# lis2dh_spi.net
KiCad netlist of a schematic drawn in Altium Designer
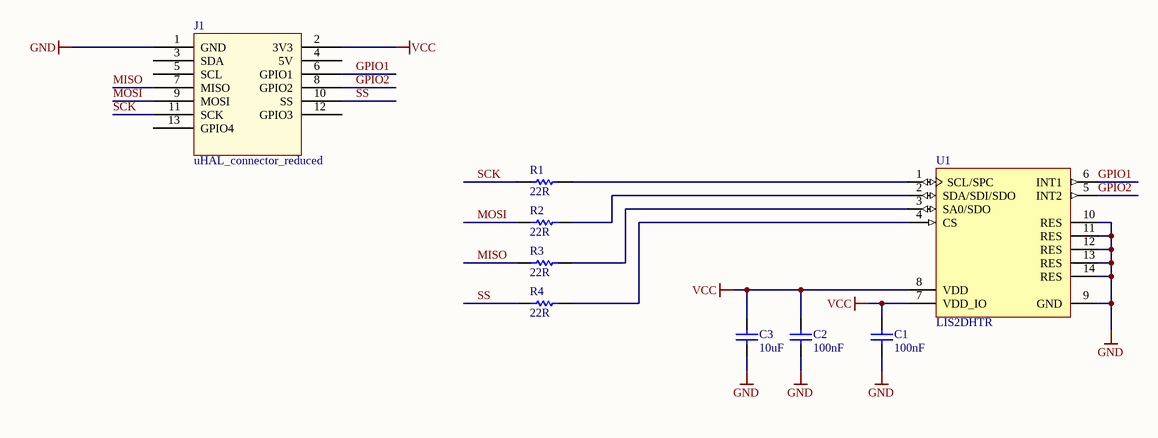
[diagram p0: lis2dh_spi.SchDoc]

(export (version "E")
  (design (tool "Eeschema 10.0.6"))
  (components
    (comp (ref "C1")
      (value "Murata GCM188R71H104KA57D")
      (footprint "CAPC1608X90X35ML10T15")
      (description "CAP CER 0.1UF 50V 10% X7R 0603")
      (fields (field (name "CAPACITANCE") "100nF"))
      (libsource (lib "CommunityVault") (part "CMP-119667-3"))
    )
    (comp (ref "C2")
      (value "Murata GCM188R71H104KA57D")
      (footprint "CAPC1608X90X35ML10T15")
      (description "CAP CER 0.1UF 50V 10% X7R 0603")
      (fields (field (name "CAPACITANCE") "100nF"))
      (libsource (lib "CommunityVault") (part "CMP-119667-3"))
    )
    (comp (ref "C3")
      (value "Murata GCM188R71H104KA57D")
      (footprint "CAPC1608X90X35ML10T15")
      (description "CAP CER 0.1UF 50V 10% X7R 0603")
      (fields (field (name "CAPACITANCE") "10uF"))
      (libsource (lib "CommunityVault") (part "CMP-119667-3"))
    )
    (comp (ref "J1")
      (value "uHAL_connector_reduced")
      (footprint "PCB-45ncoppm4oopozvqifsq-1")
      (description "connector for uHAL with reduced pin number")
      (libsource (lib "CommunityVault") (part "CMP-2q23h2cwhjlfm8s6r7i8-1"))
    )
    (comp (ref "R1")
      (value "22R")
      (footprint "RESC1608X05N")
      (description "RCA Series 0603 0.1 W 0 O Jumper Surface Mount Thick Film Chip Resistor")
      (fields (field (name "MANUFACTURER PART NUMBER") "RCA06030000ZSEA"))
      (libsource (lib "CommunityVault") (part "SYM-31acf99032f6ee6b-1"))
    )
    (comp (ref "R2")
      (value "22R")
      (footprint "RESC1608X05N")
      (description "RCA Series 0603 0.1 W 0 O Jumper Surface Mount Thick Film Chip Resistor")
      (fields (field (name "MANUFACTURER PART NUMBER") "RCA06030000ZSEA"))
      (libsource (lib "CommunityVault") (part "SYM-31acf99032f6ee6b-1"))
    )
    (comp (ref "R3")
      (value "22R")
      (footprint "RESC1608X05N")
      (description "RCA Series 0603 0.1 W 0 O Jumper Surface Mount Thick Film Chip Resistor")
      (fields (field (name "MANUFACTURER PART NUMBER") "RCA06030000ZSEA"))
      (libsource (lib "CommunityVault") (part "SYM-31acf99032f6ee6b-1"))
    )
    (comp (ref "R4")
      (value "22R")
      (footprint "RESC1608X05N")
      (description "RCA Series 0603 0.1 W 0 O Jumper Surface Mount Thick Film Chip Resistor")
      (fields (field (name "MANUFACTURER PART NUMBER") "RCA06030000ZSEA"))
      (libsource (lib "CommunityVault") (part "SYM-31acf99032f6ee6b-1"))
    )
    (comp (ref "U1")
      (value "LIS2DHTR")
      (footprint "LGA-14_N")
      (libsource (lib "CommunityVault") (part "STM-LIS2DH-LGA-14"))
    )
  )
  (nets
    (net (code "1") (name "/GPIO1") (class "Default")
      (node (ref "J1") (pin "6") (pinfunction "GPIO1_6") (pintype "passive"))
      (node (ref "U1") (pin "6") (pinfunction "INT1_6") (pintype "output"))
    )
    (net (code "2") (name "/GPIO2") (class "Default")
      (node (ref "J1") (pin "8") (pinfunction "GPIO2_8") (pintype "passive"))
      (node (ref "U1") (pin "5") (pinfunction "INT2_5") (pintype "output"))
    )
    (net (code "3") (name "/MISO") (class "Default")
      (node (ref "J1") (pin "7") (pinfunction "MISO_7") (pintype "passive"))
      (node (ref "R3") (pin "2") (pinfunction "2_2") (pintype "passive"))
    )
    (net (code "4") (name "/MOSI") (class "Default")
      (node (ref "J1") (pin "9") (pinfunction "MOSI_9") (pintype "passive"))
      (node (ref "R2") (pin "2") (pinfunction "2_2") (pintype "passive"))
    )
    (net (code "5") (name "/SCK") (class "Default")
      (node (ref "J1") (pin "11") (pinfunction "SCK_11") (pintype "passive"))
      (node (ref "R1") (pin "2") (pinfunction "2_2") (pintype "passive"))
    )
    (net (code "6") (name "/SS") (class "Default")
      (node (ref "J1") (pin "10") (pinfunction "SS_10") (pintype "passive"))
      (node (ref "R4") (pin "2") (pinfunction "2_2") (pintype "passive"))
    )
    (net (code "7") (name "GND") (class "Default")
      (node (ref "C1") (pin "2") (pinfunction "2_2") (pintype "passive"))
      (node (ref "C2") (pin "2") (pinfunction "2_2") (pintype "passive"))
      (node (ref "C3") (pin "2") (pinfunction "2_2") (pintype "passive"))
      (node (ref "J1") (pin "1") (pinfunction "GND_1") (pintype "passive"))
      (node (ref "U1") (pin "10") (pinfunction "RES_10") (pintype "power_in"))
      (node (ref "U1") (pin "11") (pinfunction "RES_11") (pintype "power_in"))
      (node (ref "U1") (pin "12") (pinfunction "RES_12") (pintype "power_in"))
      (node (ref "U1") (pin "13") (pinfunction "RES_13") (pintype "power_in"))
      (node (ref "U1") (pin "14") (pinfunction "RES_14") (pintype "power_in"))
      (node (ref "U1") (pin "9") (pinfunction "GND_9") (pintype "power_in"))
    )
    (net (code "8") (name "Net-(U1-CS)") (class "Default")
      (node (ref "R4") (pin "1") (pinfunction "1_1") (pintype "passive"))
      (node (ref "U1") (pin "4") (pinfunction "CS_4") (pintype "input"))
    )
    (net (code "9") (name "Net-(U1-SA0{slash}SDO)") (class "Default")
      (node (ref "R3") (pin "1") (pinfunction "1_1") (pintype "passive"))
      (node (ref "U1") (pin "3") (pinfunction "SA0/SDO_3") (pintype "bidirectional"))
    )
    (net (code "10") (name "Net-(U1-SCL{slash}SPC)") (class "Default")
      (node (ref "R1") (pin "1") (pinfunction "1_1") (pintype "passive"))
      (node (ref "U1") (pin "1") (pinfunction "SCL/SPC_1") (pintype "bidirectional"))
    )
    (net (code "11") (name "Net-(U1-SDA{slash}SDI{slash}SDO)") (class "Default")
      (node (ref "R2") (pin "1") (pinfunction "1_1") (pintype "passive"))
      (node (ref "U1") (pin "2") (pinfunction "SDA/SDI/SDO_2") (pintype "bidirectional"))
    )
    (net (code "12") (name "VCC") (class "Default")
      (node (ref "C1") (pin "1") (pinfunction "1_1") (pintype "passive"))
      (node (ref "C2") (pin "1") (pinfunction "1_1") (pintype "passive"))
      (node (ref "C3") (pin "1") (pinfunction "1_1") (pintype "passive"))
      (node (ref "J1") (pin "2") (pinfunction "3V3_2") (pintype "passive"))
      (node (ref "U1") (pin "7") (pinfunction "VDD_IO_7") (pintype "power_in"))
      (node (ref "U1") (pin "8") (pinfunction "VDD_8") (pintype "power_in"))
    )
    (net (code "13") (name "unconnected-(J1-5V-Pad4)") (class "Default")
      (node (ref "J1") (pin "4") (pinfunction "5V_4") (pintype "passive"))
    )
    (net (code "14") (name "unconnected-(J1-GPIO3-Pad12)") (class "Default")
      (node (ref "J1") (pin "12") (pinfunction "GPIO3_12") (pintype "passive"))
    )
    (net (code "15") (name "unconnected-(J1-GPIO4-Pad13)") (class "Default")
      (node (ref "J1") (pin "13") (pinfunction "GPIO4_13") (pintype "passive"))
    )
    (net (code "16") (name "unconnected-(J1-SCL-Pad5)") (class "Default")
      (node (ref "J1") (pin "5") (pinfunction "SCL_5") (pintype "passive"))
    )
    (net (code "17") (name "unconnected-(J1-SDA-Pad3)") (class "Default")
      (node (ref "J1") (pin "3") (pinfunction "SDA_3") (pintype "passive"))
    )
  )
)
